# SoM-Connectors.net
KiCad netlist of a schematic drawn in Altium Designer
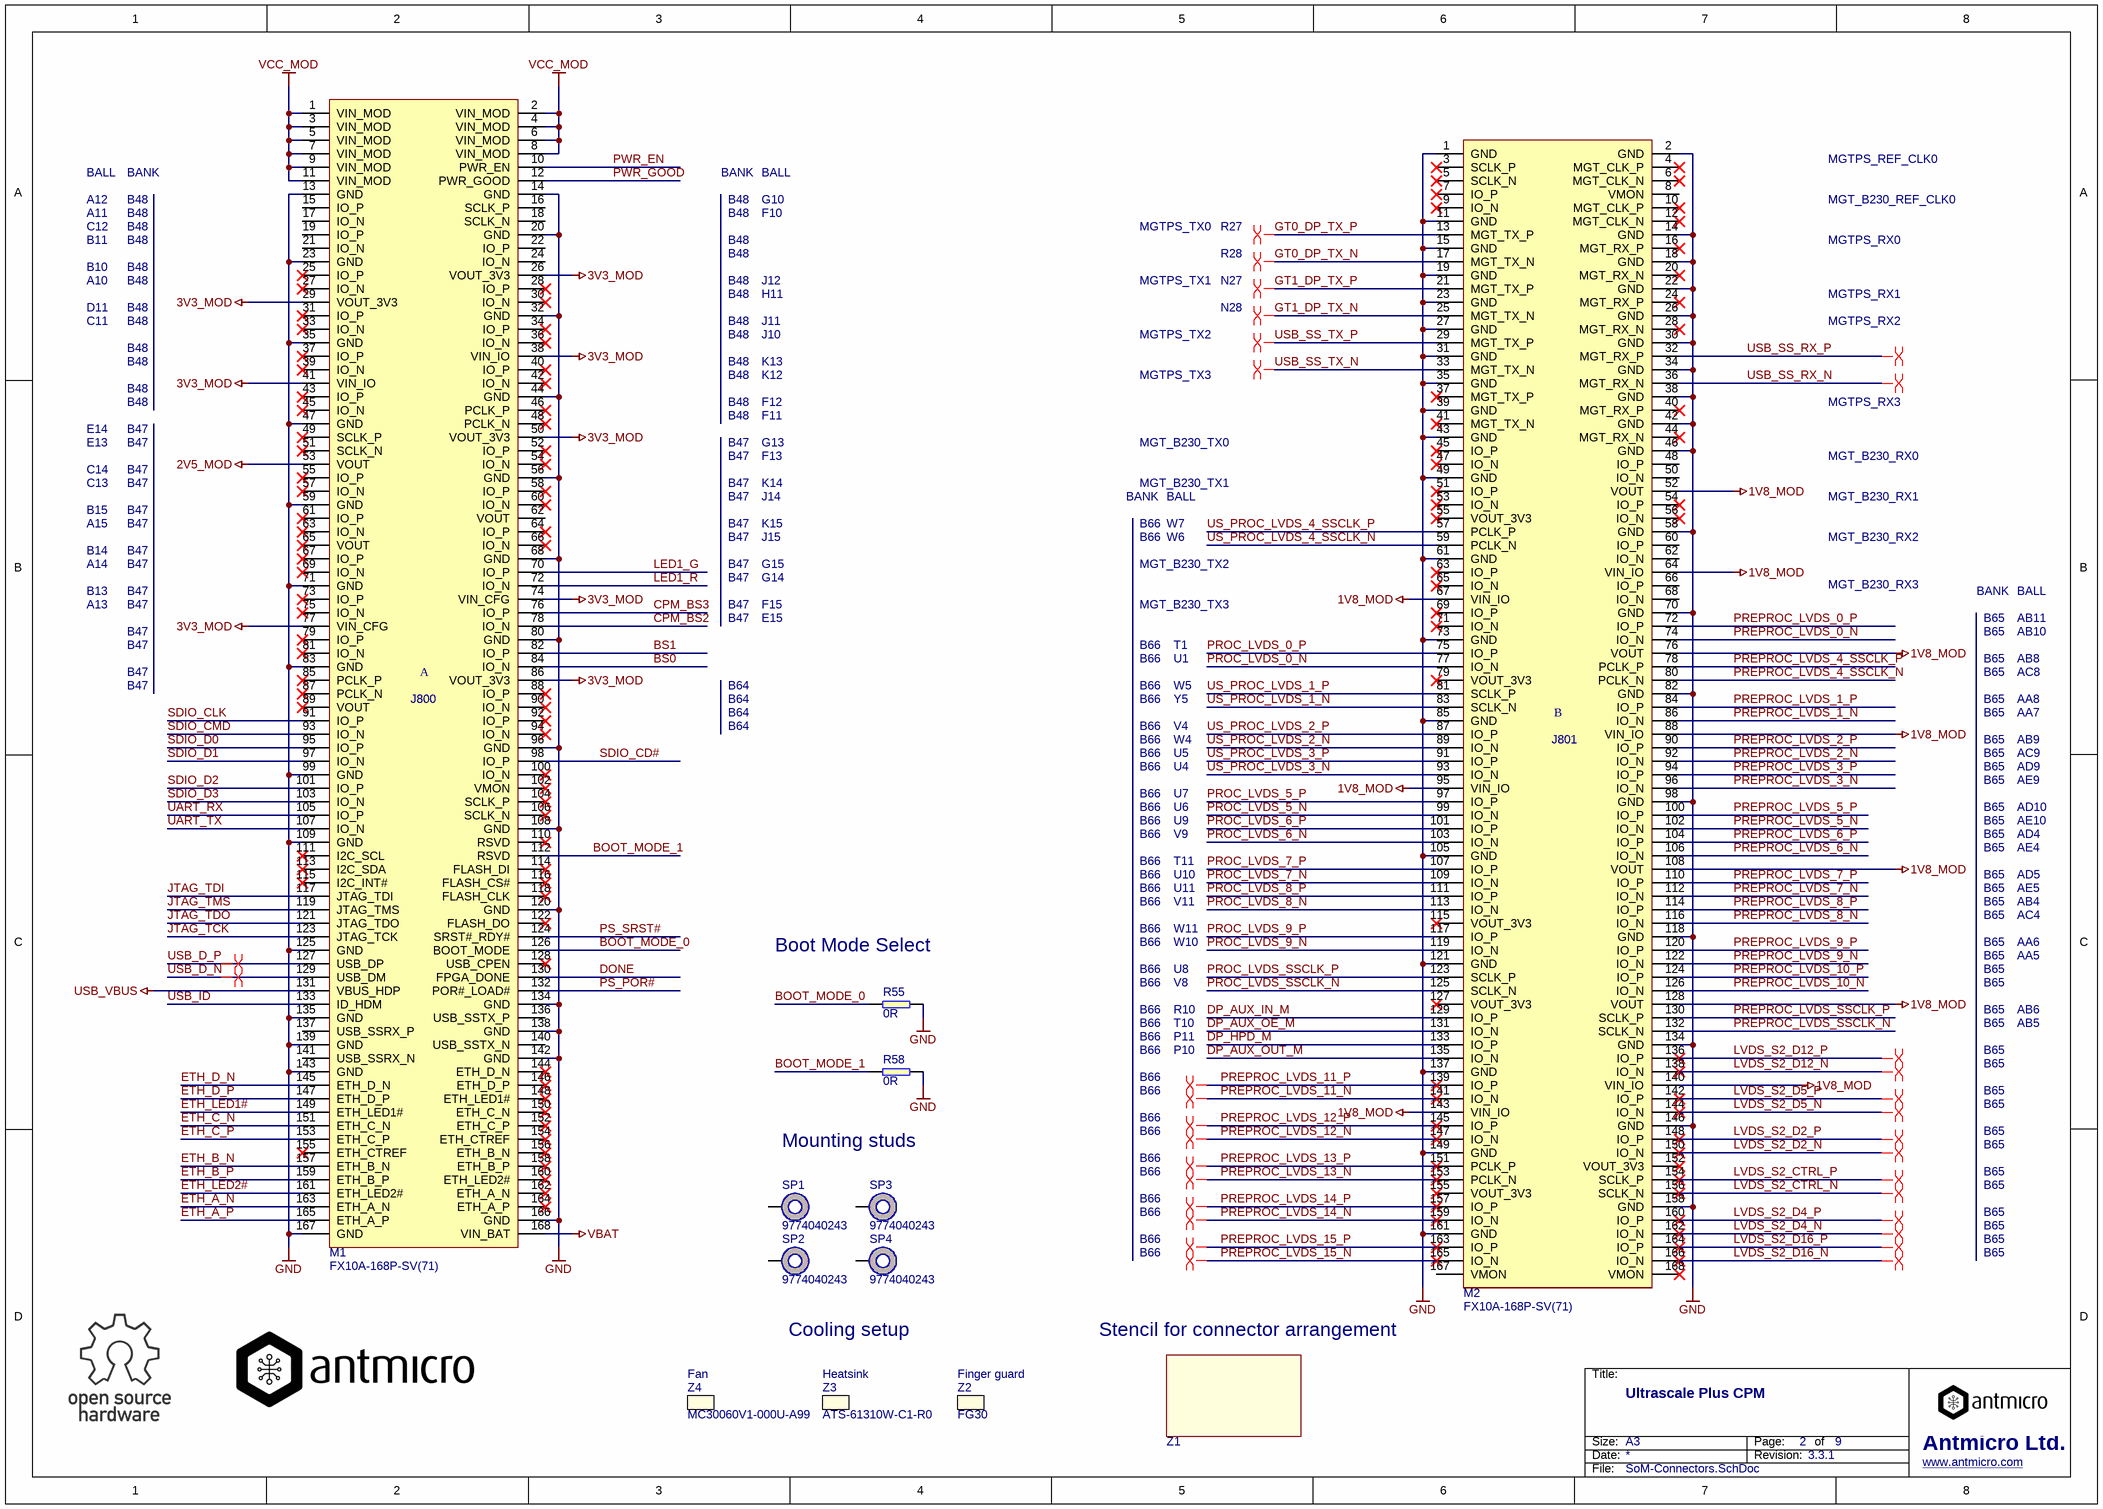
[diagram p0: SoM-Connectors.SchDoc]

(export (version "E")
  (design (tool "Eeschema 10.0.6"))
  (components
    (comp (ref "M1")
      (value "FX10A-168P-SV(71)")
      (footprint "HIROSE_FX10A-168P-SV(71)")
      (description "Enclustra Mercury Ultrascale connector")
      (fields (field (name "PART NUMBER") "Mercury_US1_A") (field (name "MANUFACTURER") "Hirose"))
      (libsource (lib "US-Plus-CPM") (part "Mercury_US1_A"))
    )
    (comp (ref "M2")
      (value "FX10A-168P-SV(71)")
      (footprint "HIROSE_FX10A-168P-SV(71)")
      (description "Enclustra Mercury Ultrascale connector")
      (fields (field (name "PART NUMBER") "Mercury_US1_B") (field (name "MANUFACTURER") "Hirose"))
      (libsource (lib "US-Plus-CPM") (part "Mercury_US1_B"))
    )
    (comp (ref "R55")
      (value "0R")
      (footprint "0603")
      (description "SMT Resistor 0R 0603")
      (fields (field (name "PART NUMBER") "R_0R_0603") (field (name "MANUFACTURER") "BOURNS"))
      (libsource (lib "US-Plus-CPM") (part "R"))
    )
    (comp (ref "R58")
      (value "0R")
      (footprint "0603")
      (description "SMT Resistor 0R 0603")
      (fields (field (name "PART NUMBER") "R_0R_0603") (field (name "MANUFACTURER") "BOURNS"))
      (libsource (lib "US-Plus-CPM") (part "R"))
    )
    (comp (ref "SP1")
      (value "9774040243")
      (footprint "M2-4mm")
      (description "M2x4")
      (fields (field (name "PART NUMBER") "WE_9774040243") (field (name "MANUFACTURER") "WURTH ELEKTRONIK"))
      (libsource (lib "US-Plus-CPM") (part "SPACER"))
    )
    (comp (ref "SP2")
      (value "9774040243")
      (footprint "M2-4mm")
      (description "M2x4")
      (fields (field (name "PART NUMBER") "WE_9774040243") (field (name "MANUFACTURER") "WURTH ELEKTRONIK"))
      (libsource (lib "US-Plus-CPM") (part "SPACER"))
    )
    (comp (ref "SP3")
      (value "9774040243")
      (footprint "M2-4mm")
      (description "M2x4")
      (fields (field (name "PART NUMBER") "WE_9774040243") (field (name "MANUFACTURER") "WURTH ELEKTRONIK"))
      (libsource (lib "US-Plus-CPM") (part "SPACER"))
    )
    (comp (ref "SP4")
      (value "9774040243")
      (footprint "M2-4mm")
      (description "M2x4")
      (fields (field (name "PART NUMBER") "WE_9774040243") (field (name "MANUFACTURER") "WURTH ELEKTRONIK"))
      (libsource (lib "US-Plus-CPM") (part "SPACER"))
    )
    (comp (ref "Z1")
      (value "Mechanical")
      (footprint "mercury_74x54_module")
      (fields (field (name "PART NUMBER") "MercuryModule_74x54"))
      (libsource (lib "US-Plus-CPM") (part "enclustra_mercury_74x54_module"))
    )
    (comp (ref "Z2")
      (value "FG30")
      (description "Fan Finger Guard, Grille, 30mm 30mm 24mm, steel")
      (fields (field (name "MANUFACTURER") "SEPA"))
      (libsource (lib "US-Plus-CPM") (part "GENERIC_BOM_ONLY"))
    )
    (comp (ref "Z3")
      (value "ATS-61310W-C1-R0")
      (description "Heat Sinks FANSINK ASSY 30.25 X 30.25 X 24.5 (MM)")
      (fields (field (name "MANUFACTURER") "Advanced Thermal Solution"))
      (libsource (lib "US-Plus-CPM") (part "GENERIC_BOM_ONLY"))
    )
    (comp (ref "Z4")
      (value "MC30060V1-000U-A99")
      (description "Fan: DC; axial; 5VDC; 30x30x6mm; 8.32m3/h; 28dBA; Vapo; 3.55mmH2O")
      (fields (field (name "MANUFACTURER") "SUNON"))
      (libsource (lib "US-Plus-CPM") (part "GENERIC_BOM_ONLY"))
    )
  )
  (nets
    (net (code "1") (name "/BOOT_MODE_0") (class "Default")
      (node (ref "M1") (pin "126") (pinfunction "BOOT_MODE_126") (pintype "passive"))
      (node (ref "R55") (pin "1") (pintype "passive"))
    )
    (net (code "2") (name "/BOOT_MODE_1") (class "Default")
      (node (ref "M1") (pin "112") (pinfunction "RSVD_112") (pintype "passive"))
      (node (ref "R58") (pin "1") (pintype "passive"))
    )
    (net (code "3") (name "/BS0") (class "Default")
      (node (ref "M1") (pin "84") (pinfunction "IO_N_84") (pintype "passive"))
    )
    (net (code "4") (name "/BS1") (class "Default")
      (node (ref "M1") (pin "82") (pinfunction "IO_P_82") (pintype "passive"))
    )
    (net (code "5") (name "/CPM_BS2") (class "Default")
      (node (ref "M1") (pin "78") (pinfunction "IO_N_78") (pintype "passive"))
    )
    (net (code "6") (name "/CPM_BS3") (class "Default")
      (node (ref "M1") (pin "76") (pinfunction "IO_P_76") (pintype "passive"))
    )
    (net (code "7") (name "/DONE") (class "Default")
      (node (ref "M1") (pin "130") (pinfunction "FPGA_DONE_130") (pintype "passive"))
    )
    (net (code "8") (name "/DP_AUX_IN_M") (class "Default")
      (node (ref "M2") (pin "129") (pinfunction "IO_P_129") (pintype "passive"))
    )
    (net (code "9") (name "/DP_AUX_OE_M") (class "Default")
      (node (ref "M2") (pin "131") (pinfunction "IO_N_131") (pintype "passive"))
    )
    (net (code "10") (name "/DP_AUX_OUT_M") (class "Default")
      (node (ref "M2") (pin "135") (pinfunction "IO_N_135") (pintype "passive"))
    )
    (net (code "11") (name "/DP_HPD_M") (class "Default")
      (node (ref "M2") (pin "133") (pinfunction "IO_P_133") (pintype "passive"))
    )
    (net (code "12") (name "/ETH_A_N") (class "Default")
      (node (ref "M1") (pin "163") (pinfunction "ETH_A_N_163") (pintype "passive"))
    )
    (net (code "13") (name "/ETH_A_P") (class "Default")
      (node (ref "M1") (pin "165") (pinfunction "ETH_A_P_165") (pintype "passive"))
    )
    (net (code "14") (name "/ETH_B_N") (class "Default")
      (node (ref "M1") (pin "157") (pinfunction "ETH_B_N_157") (pintype "passive"))
    )
    (net (code "15") (name "/ETH_B_P") (class "Default")
      (node (ref "M1") (pin "159") (pinfunction "ETH_B_P_159") (pintype "passive"))
    )
    (net (code "16") (name "/ETH_C_N") (class "Default")
      (node (ref "M1") (pin "151") (pinfunction "ETH_C_N_151") (pintype "passive"))
    )
    (net (code "17") (name "/ETH_C_P") (class "Default")
      (node (ref "M1") (pin "153") (pinfunction "ETH_C_P_153") (pintype "passive"))
    )
    (net (code "18") (name "/ETH_D_N") (class "Default")
      (node (ref "M1") (pin "145") (pinfunction "ETH_D_N_145") (pintype "passive"))
    )
    (net (code "19") (name "/ETH_D_P") (class "Default")
      (node (ref "M1") (pin "147") (pinfunction "ETH_D_P_147") (pintype "passive"))
    )
    (net (code "20") (name "/ETH_LED1#") (class "Default")
      (node (ref "M1") (pin "149") (pinfunction "ETH_LED1#_149") (pintype "passive"))
    )
    (net (code "21") (name "/ETH_LED2#") (class "Default")
      (node (ref "M1") (pin "161") (pinfunction "ETH_LED2#_161") (pintype "passive"))
    )
    (net (code "22") (name "/GT0_DP_TX_N") (class "Default")
      (node (ref "M2") (pin "17") (pinfunction "MGT_TX_N_17") (pintype "passive"))
    )
    (net (code "23") (name "/GT0_DP_TX_P") (class "Default")
      (node (ref "M2") (pin "13") (pinfunction "MGT_TX_P_13") (pintype "passive"))
    )
    (net (code "24") (name "/GT1_DP_TX_N") (class "Default")
      (node (ref "M2") (pin "25") (pinfunction "MGT_TX_N_25") (pintype "passive"))
    )
    (net (code "25") (name "/GT1_DP_TX_P") (class "Default")
      (node (ref "M2") (pin "21") (pinfunction "MGT_TX_P_21") (pintype "passive"))
    )
    (net (code "26") (name "/JTAG_TCK") (class "Default")
      (node (ref "M1") (pin "123") (pinfunction "JTAG_TCK_123") (pintype "passive"))
    )
    (net (code "27") (name "/JTAG_TDI") (class "Default")
      (node (ref "M1") (pin "117") (pinfunction "JTAG_TDI_117") (pintype "passive"))
    )
    (net (code "28") (name "/JTAG_TDO") (class "Default")
      (node (ref "M1") (pin "121") (pinfunction "JTAG_TDO_121") (pintype "passive"))
    )
    (net (code "29") (name "/JTAG_TMS") (class "Default")
      (node (ref "M1") (pin "119") (pinfunction "JTAG_TMS_119") (pintype "passive"))
    )
    (net (code "30") (name "/LED1_G") (class "Default")
      (node (ref "M1") (pin "70") (pinfunction "IO_P_70") (pintype "passive"))
    )
    (net (code "31") (name "/LED1_R") (class "Default")
      (node (ref "M1") (pin "72") (pinfunction "IO_N_72") (pintype "passive"))
    )
    (net (code "32") (name "/LVDS_S2_CTRL_N") (class "Default")
      (node (ref "M2") (pin "156") (pinfunction "SCLK_N_156") (pintype "passive+no_connect"))
    )
    (net (code "33") (name "/LVDS_S2_CTRL_P") (class "Default")
      (node (ref "M2") (pin "154") (pinfunction "SCLK_P_154") (pintype "passive+no_connect"))
    )
    (net (code "34") (name "/LVDS_S2_D2_N") (class "Default")
      (node (ref "M2") (pin "150") (pinfunction "IO_N_150") (pintype "passive+no_connect"))
    )
    (net (code "35") (name "/LVDS_S2_D2_P") (class "Default")
      (node (ref "M2") (pin "148") (pinfunction "IO_P_148") (pintype "passive+no_connect"))
    )
    (net (code "36") (name "/LVDS_S2_D4_N") (class "Default")
      (node (ref "M2") (pin "162") (pinfunction "IO_N_162") (pintype "passive+no_connect"))
    )
    (net (code "37") (name "/LVDS_S2_D4_P") (class "Default")
      (node (ref "M2") (pin "160") (pinfunction "IO_P_160") (pintype "passive+no_connect"))
    )
    (net (code "38") (name "/LVDS_S2_D5_N") (class "Default")
      (node (ref "M2") (pin "144") (pinfunction "IO_N_144") (pintype "passive+no_connect"))
    )
    (net (code "39") (name "/LVDS_S2_D5_P") (class "Default")
      (node (ref "M2") (pin "142") (pinfunction "IO_P_142") (pintype "passive+no_connect"))
    )
    (net (code "40") (name "/LVDS_S2_D12_N") (class "Default")
      (node (ref "M2") (pin "138") (pinfunction "IO_N_138") (pintype "passive+no_connect"))
    )
    (net (code "41") (name "/LVDS_S2_D12_P") (class "Default")
      (node (ref "M2") (pin "136") (pinfunction "IO_P_136") (pintype "passive+no_connect"))
    )
    (net (code "42") (name "/LVDS_S2_D16_N") (class "Default")
      (node (ref "M2") (pin "166") (pinfunction "IO_N_166") (pintype "passive+no_connect"))
    )
    (net (code "43") (name "/LVDS_S2_D16_P") (class "Default")
      (node (ref "M2") (pin "164") (pinfunction "IO_P_164") (pintype "passive+no_connect"))
    )
    (net (code "44") (name "/PREPROC_LVDS_0_N") (class "Default")
      (node (ref "M2") (pin "74") (pinfunction "IO_N_74") (pintype "passive"))
    )
    (net (code "45") (name "/PREPROC_LVDS_0_P") (class "Default")
      (node (ref "M2") (pin "72") (pinfunction "IO_P_72") (pintype "passive"))
    )
    (net (code "46") (name "/PREPROC_LVDS_1_N") (class "Default")
      (node (ref "M2") (pin "86") (pinfunction "IO_N_86") (pintype "passive"))
    )
    (net (code "47") (name "/PREPROC_LVDS_1_P") (class "Default")
      (node (ref "M2") (pin "84") (pinfunction "IO_P_84") (pintype "passive"))
    )
    (net (code "48") (name "/PREPROC_LVDS_2_N") (class "Default")
      (node (ref "M2") (pin "92") (pinfunction "IO_N_92") (pintype "passive"))
    )
    (net (code "49") (name "/PREPROC_LVDS_2_P") (class "Default")
      (node (ref "M2") (pin "90") (pinfunction "IO_P_90") (pintype "passive"))
    )
    (net (code "50") (name "/PREPROC_LVDS_3_N") (class "Default")
      (node (ref "M2") (pin "96") (pinfunction "IO_N_96") (pintype "passive"))
    )
    (net (code "51") (name "/PREPROC_LVDS_3_P") (class "Default")
      (node (ref "M2") (pin "94") (pinfunction "IO_P_94") (pintype "passive"))
    )
    (net (code "52") (name "/PREPROC_LVDS_4_SSCLK_N") (class "Default")
      (node (ref "M2") (pin "80") (pinfunction "PCLK_N_80") (pintype "passive"))
    )
    (net (code "53") (name "/PREPROC_LVDS_4_SSCLK_P") (class "Default")
      (node (ref "M2") (pin "78") (pinfunction "PCLK_P_78") (pintype "passive"))
    )
    (net (code "54") (name "/PREPROC_LVDS_5_N") (class "Default")
      (node (ref "M2") (pin "102") (pinfunction "IO_N_102") (pintype "passive"))
    )
    (net (code "55") (name "/PREPROC_LVDS_5_P") (class "Default")
      (node (ref "M2") (pin "100") (pinfunction "IO_P_100") (pintype "passive"))
    )
    (net (code "56") (name "/PREPROC_LVDS_6_N") (class "Default")
      (node (ref "M2") (pin "106") (pinfunction "IO_N_106") (pintype "passive"))
    )
    (net (code "57") (name "/PREPROC_LVDS_6_P") (class "Default")
      (node (ref "M2") (pin "104") (pinfunction "IO_P_104") (pintype "passive"))
    )
    (net (code "58") (name "/PREPROC_LVDS_7_N") (class "Default")
      (node (ref "M2") (pin "112") (pinfunction "IO_N_112") (pintype "passive"))
    )
    (net (code "59") (name "/PREPROC_LVDS_7_P") (class "Default")
      (node (ref "M2") (pin "110") (pinfunction "IO_P_110") (pintype "passive"))
    )
    (net (code "60") (name "/PREPROC_LVDS_8_N") (class "Default")
      (node (ref "M2") (pin "116") (pinfunction "IO_N_116") (pintype "passive"))
    )
    (net (code "61") (name "/PREPROC_LVDS_8_P") (class "Default")
      (node (ref "M2") (pin "114") (pinfunction "IO_P_114") (pintype "passive"))
    )
    (net (code "62") (name "/PREPROC_LVDS_9_N") (class "Default")
      (node (ref "M2") (pin "122") (pinfunction "IO_N_122") (pintype "passive"))
    )
    (net (code "63") (name "/PREPROC_LVDS_9_P") (class "Default")
      (node (ref "M2") (pin "120") (pinfunction "IO_P_120") (pintype "passive"))
    )
    (net (code "64") (name "/PREPROC_LVDS_10_N") (class "Default")
      (node (ref "M2") (pin "126") (pinfunction "IO_N_126") (pintype "passive"))
    )
    (net (code "65") (name "/PREPROC_LVDS_10_P") (class "Default")
      (node (ref "M2") (pin "124") (pinfunction "IO_P_124") (pintype "passive"))
    )
    (net (code "66") (name "/PREPROC_LVDS_11_N") (class "Default")
      (node (ref "M2") (pin "141") (pinfunction "IO_N_141") (pintype "passive+no_connect"))
    )
    (net (code "67") (name "/PREPROC_LVDS_11_P") (class "Default")
      (node (ref "M2") (pin "139") (pinfunction "IO_P_139") (pintype "passive+no_connect"))
    )
    (net (code "68") (name "/PREPROC_LVDS_12_N") (class "Default")
      (node (ref "M2") (pin "147") (pinfunction "IO_N_147") (pintype "passive+no_connect"))
    )
    (net (code "69") (name "/PREPROC_LVDS_12_P") (class "Default")
      (node (ref "M2") (pin "145") (pinfunction "IO_P_145") (pintype "passive+no_connect"))
    )
    (net (code "70") (name "/PREPROC_LVDS_13_N") (class "Default")
      (node (ref "M2") (pin "153") (pinfunction "PCLK_N_153") (pintype "passive+no_connect"))
    )
    (net (code "71") (name "/PREPROC_LVDS_13_P") (class "Default")
      (node (ref "M2") (pin "151") (pinfunction "PCLK_P_151") (pintype "passive+no_connect"))
    )
    (net (code "72") (name "/PREPROC_LVDS_14_N") (class "Default")
      (node (ref "M2") (pin "159") (pinfunction "IO_N_159") (pintype "passive+no_connect"))
    )
    (net (code "73") (name "/PREPROC_LVDS_14_P") (class "Default")
      (node (ref "M2") (pin "157") (pinfunction "IO_P_157") (pintype "passive+no_connect"))
    )
    (net (code "74") (name "/PREPROC_LVDS_15_N") (class "Default")
      (node (ref "M2") (pin "165") (pinfunction "IO_N_165") (pintype "passive+no_connect"))
    )
    (net (code "75") (name "/PREPROC_LVDS_15_P") (class "Default")
      (node (ref "M2") (pin "163") (pinfunction "IO_P_163") (pintype "passive+no_connect"))
    )
    (net (code "76") (name "/PREPROC_LVDS_SSCLK_N") (class "Default")
      (node (ref "M2") (pin "132") (pinfunction "SCLK_N_132") (pintype "passive"))
    )
    (net (code "77") (name "/PREPROC_LVDS_SSCLK_P") (class "Default")
      (node (ref "M2") (pin "130") (pinfunction "SCLK_P_130") (pintype "passive"))
    )
    (net (code "78") (name "/PROC_LVDS_0_N") (class "Default")
      (node (ref "M2") (pin "77") (pinfunction "IO_N_77") (pintype "passive"))
    )
    (net (code "79") (name "/PROC_LVDS_0_P") (class "Default")
      (node (ref "M2") (pin "75") (pinfunction "IO_P_75") (pintype "passive"))
    )
    (net (code "80") (name "/PROC_LVDS_5_N") (class "Default")
      (node (ref "M2") (pin "99") (pinfunction "IO_N_99") (pintype "passive"))
    )
    (net (code "81") (name "/PROC_LVDS_5_P") (class "Default")
      (node (ref "M2") (pin "97") (pinfunction "IO_P_97") (pintype "passive"))
    )
    (net (code "82") (name "/PROC_LVDS_6_N") (class "Default")
      (node (ref "M2") (pin "103") (pinfunction "IO_N_103") (pintype "passive"))
    )
    (net (code "83") (name "/PROC_LVDS_6_P") (class "Default")
      (node (ref "M2") (pin "101") (pinfunction "IO_P_101") (pintype "passive"))
    )
    (net (code "84") (name "/PROC_LVDS_7_N") (class "Default")
      (node (ref "M2") (pin "109") (pinfunction "IO_N_109") (pintype "passive"))
    )
    (net (code "85") (name "/PROC_LVDS_7_P") (class "Default")
      (node (ref "M2") (pin "107") (pinfunction "IO_P_107") (pintype "passive"))
    )
    (net (code "86") (name "/PROC_LVDS_8_N") (class "Default")
      (node (ref "M2") (pin "113") (pinfunction "IO_N_113") (pintype "passive"))
    )
    (net (code "87") (name "/PROC_LVDS_8_P") (class "Default")
      (node (ref "M2") (pin "111") (pinfunction "IO_P_111") (pintype "passive"))
    )
    (net (code "88") (name "/PROC_LVDS_9_N") (class "Default")
      (node (ref "M2") (pin "119") (pinfunction "IO_N_119") (pintype "passive"))
    )
    (net (code "89") (name "/PROC_LVDS_9_P") (class "Default")
      (node (ref "M2") (pin "117") (pinfunction "IO_P_117") (pintype "passive"))
    )
    (net (code "90") (name "/PROC_LVDS_SSCLK_N") (class "Default")
      (node (ref "M2") (pin "125") (pinfunction "SCLK_N_125") (pintype "passive"))
    )
    (net (code "91") (name "/PROC_LVDS_SSCLK_P") (class "Default")
      (node (ref "M2") (pin "123") (pinfunction "SCLK_P_123") (pintype "passive"))
    )
    (net (code "92") (name "/PS_POR#") (class "Default")
      (node (ref "M1") (pin "132") (pinfunction "POR#_LOAD#_132") (pintype "passive"))
    )
    (net (code "93") (name "/PS_SRST#") (class "Default")
      (node (ref "M1") (pin "124") (pinfunction "SRST#_RDY#_124") (pintype "passive"))
    )
    (net (code "94") (name "/PWR_EN") (class "Default")
      (node (ref "M1") (pin "10") (pinfunction "PWR_EN_10") (pintype "passive"))
    )
    (net (code "95") (name "/PWR_GOOD") (class "Default")
      (node (ref "M1") (pin "12") (pinfunction "PWR_GOOD_12") (pintype "passive"))
    )
    (net (code "96") (name "/SDIO_CD#") (class "Default")
      (node (ref "M1") (pin "98") (pinfunction "IO_P_98") (pintype "passive"))
    )
    (net (code "97") (name "/SDIO_CLK") (class "Default")
      (node (ref "M1") (pin "91") (pinfunction "IO_P_91") (pintype "passive"))
    )
    (net (code "98") (name "/SDIO_CMD") (class "Default")
      (node (ref "M1") (pin "93") (pinfunction "IO_N_93") (pintype "passive"))
    )
    (net (code "99") (name "/SDIO_D0") (class "Default")
      (node (ref "M1") (pin "95") (pinfunction "IO_P_95") (pintype "passive"))
    )
    (net (code "100") (name "/SDIO_D1") (class "Default")
      (node (ref "M1") (pin "97") (pinfunction "IO_N_97") (pintype "passive"))
    )
    (net (code "101") (name "/SDIO_D2") (class "Default")
      (node (ref "M1") (pin "101") (pinfunction "IO_P_101") (pintype "passive"))
    )
    (net (code "102") (name "/SDIO_D3") (class "Default")
      (node (ref "M1") (pin "103") (pinfunction "IO_N_103") (pintype "passive"))
    )
    (net (code "103") (name "/UART_RX") (class "Default")
      (node (ref "M1") (pin "105") (pinfunction "IO_P_105") (pintype "passive"))
    )
    (net (code "104") (name "/UART_TX") (class "Default")
      (node (ref "M1") (pin "107") (pinfunction "IO_N_107") (pintype "passive"))
    )
    (net (code "105") (name "/USB_D_N") (class "Default")
      (node (ref "M1") (pin "129") (pinfunction "USB_DM_129") (pintype "passive"))
    )
    (net (code "106") (name "/USB_D_P") (class "Default")
      (node (ref "M1") (pin "127") (pinfunction "USB_DP_127") (pintype "passive"))
    )
    (net (code "107") (name "/USB_ID") (class "Default")
      (node (ref "M1") (pin "133") (pinfunction "ID_HDM_133") (pintype "passive"))
    )
    (net (code "108") (name "/USB_SS_RX_N") (class "Default")
      (node (ref "M2") (pin "36") (pinfunction "MGT_RX_N_36") (pintype "passive"))
    )
    (net (code "109") (name "/USB_SS_RX_P") (class "Default")
      (node (ref "M2") (pin "32") (pinfunction "MGT_RX_P_32") (pintype "passive"))
    )
    (net (code "110") (name "/USB_SS_TX_N") (class "Default")
      (node (ref "M2") (pin "33") (pinfunction "MGT_TX_N_33") (pintype "passive"))
    )
    (net (code "111") (name "/USB_SS_TX_P") (class "Default")
      (node (ref "M2") (pin "29") (pinfunction "MGT_TX_P_29") (pintype "passive"))
    )
    (net (code "112") (name "/US_PROC_LVDS_1_N") (class "Default")
      (node (ref "M2") (pin "83") (pinfunction "SCLK_N_83") (pintype "passive"))
    )
    (net (code "113") (name "/US_PROC_LVDS_1_P") (class "Default")
      (node (ref "M2") (pin "81") (pinfunction "SCLK_P_81") (pintype "passive"))
    )
    (net (code "114") (name "/US_PROC_LVDS_2_N") (class "Default")
      (node (ref "M2") (pin "89") (pinfunction "IO_N_89") (pintype "passive"))
    )
    (net (code "115") (name "/US_PROC_LVDS_2_P") (class "Default")
      (node (ref "M2") (pin "87") (pinfunction "IO_P_87") (pintype "passive"))
    )
    (net (code "116") (name "/US_PROC_LVDS_3_N") (class "Default")
      (node (ref "M2") (pin "93") (pinfunction "IO_N_93") (pintype "passive"))
    )
    (net (code "117") (name "/US_PROC_LVDS_3_P") (class "Default")
      (node (ref "M2") (pin "91") (pinfunction "IO_P_91") (pintype "passive"))
    )
    (net (code "118") (name "/US_PROC_LVDS_4_SSCLK_N") (class "Default")
      (node (ref "M2") (pin "59") (pinfunction "PCLK_N_59") (pintype "passive"))
    )
    (net (code "119") (name "/US_PROC_LVDS_4_SSCLK_P") (class "Default")
      (node (ref "M2") (pin "57") (pinfunction "PCLK_P_57") (pintype "passive"))
    )
    (net (code "120") (name "1V8_MOD") (class "Default")
      (node (ref "M2") (pin "108") (pinfunction "VOUT_108") (pintype "passive"))
      (node (ref "M2") (pin "128") (pinfunction "VOUT_128") (pintype "passive"))
      (node (ref "M2") (pin "140") (pinfunction "VIN_IO_140") (pintype "passive"))
      (node (ref "M2") (pin "143") (pinfunction "VIN_IO_143") (pintype "passive"))
      (node (ref "M2") (pin "52") (pinfunction "VOUT_52") (pintype "passive"))
      (node (ref "M2") (pin "64") (pinfunction "VIN_IO_64") (pintype "passive"))
      (node (ref "M2") (pin "67") (pinfunction "VIN_IO_67") (pintype "passive"))
      (node (ref "M2") (pin "76") (pinfunction "VOUT_76") (pintype "passive"))
      (node (ref "M2") (pin "88") (pinfunction "VIN_IO_88") (pintype "passive"))
      (node (ref "M2") (pin "95") (pinfunction "VIN_IO_95") (pintype "passive"))
    )
    (net (code "121") (name "2V5_MOD") (class "Default")
      (node (ref "M1") (pin "53") (pinfunction "VOUT_53") (pintype "power_in"))
    )
    (net (code "122") (name "3V3_MOD") (class "Default")
      (node (ref "M1") (pin "26") (pinfunction "VOUT_3V3_26") (pintype "power_in"))
      (node (ref "M1") (pin "29") (pinfunction "VOUT_3V3_29") (pintype "power_in"))
      (node (ref "M1") (pin "38") (pinfunction "VIN_IO_38") (pintype "power_in"))
      (node (ref "M1") (pin "41") (pinfunction "VIN_IO_41") (pintype "power_in"))
      (node (ref "M1") (pin "50") (pinfunction "VOUT_3V3_50") (pintype "power_in"))
      (node (ref "M1") (pin "74") (pinfunction "VIN_CFG_74") (pintype "power_in"))
      (node (ref "M1") (pin "77") (pinfunction "VIN_CFG_77") (pintype "power_in"))
      (node (ref "M1") (pin "86") (pinfunction "VOUT_3V3_86") (pintype "power_in"))
    )
    (net (code "123") (name "GND") (class "Default")
      (node (ref "M1") (pin "108") (pinfunction "GND_108") (pintype "power_in"))
      (node (ref "M1") (pin "109") (pinfunction "GND_109") (pintype "power_in"))
      (node (ref "M1") (pin "120") (pinfunction "GND_120") (pintype "power_in"))
      (node (ref "M1") (pin "125") (pinfunction "GND_125") (pintype "power_in"))
      (node (ref "M1") (pin "13") (pinfunction "GND_13") (pintype "power_in"))
      (node (ref "M1") (pin "134") (pinfunction "GND_134") (pintype "power_in"))
      (node (ref "M1") (pin "135") (pinfunction "GND_135") (pintype "power_in"))
      (node (ref "M1") (pin "138") (pinfunction "GND_138") (pintype "power_in"))
      (node (ref "M1") (pin "139") (pinfunction "GND_139") (pintype "power_in"))
      (node (ref "M1") (pin "14") (pinfunction "GND_14") (pintype "power_in"))
      (node (ref "M1") (pin "142") (pinfunction "GND_142") (pintype "power_in"))
      (node (ref "M1") (pin "143") (pinfunction "GND_143") (pintype "power_in"))
      (node (ref "M1") (pin "166") (pinfunction "GND_166") (pintype "power_in"))
      (node (ref "M1") (pin "167") (pinfunction "GND_167") (pintype "power_in"))
      (node (ref "M1") (pin "20") (pinfunction "GND_20") (pintype "power_in"))
      (node (ref "M1") (pin "23") (pinfunction "GND_23") (pintype "power_in"))
      (node (ref "M1") (pin "32") (pinfunction "GND_32") (pintype "power_in"))
      (node (ref "M1") (pin "35") (pinfunction "GND_35") (pintype "power_in"))
      (node (ref "M1") (pin "44") (pinfunction "GND_44") (pintype "power_in"))
      (node (ref "M1") (pin "47") (pinfunction "GND_47") (pintype "power_in"))
      (node (ref "M1") (pin "56") (pinfunction "GND_56") (pintype "power_in"))
      (node (ref "M1") (pin "59") (pinfunction "GND_59") (pintype "power_in"))
      (node (ref "M1") (pin "68") (pinfunction "GND_68") (pintype "power_in"))
      (node (ref "M1") (pin "71") (pinfunction "GND_71") (pintype "power_in"))
      (node (ref "M1") (pin "80") (pinfunction "GND_80") (pintype "power_in"))
      (node (ref "M1") (pin "83") (pinfunction "GND_83") (pintype "power_in"))
      (node (ref "M1") (pin "96") (pinfunction "GND_96") (pintype "power_in"))
      (node (ref "M1") (pin "99") (pinfunction "GND_99") (pintype "power_in"))
      (node (ref "M2") (pin "1") (pinfunction "GND_1") (pintype "passive"))
      (node (ref "M2") (pin "105") (pinfunction "GND_105") (pintype "passive"))
      (node (ref "M2") (pin "11") (pinfunction "GND_11") (pintype "passive"))
      (node (ref "M2") (pin "118") (pinfunction "GND_118") (pintype "passive"))
      (node (ref "M2") (pin "121") (pinfunction "GND_121") (pintype "passive"))
      (node (ref "M2") (pin "134") (pinfunction "GND_134") (pintype "passive"))
      (node (ref "M2") (pin "137") (pinfunction "GND_137") (pintype "passive"))
      (node (ref "M2") (pin "14") (pinfunction "GND_14") (pintype "passive"))
      (node (ref "M2") (pin "146") (pinfunction "GND_146") (pintype "passive"))
      (node (ref "M2") (pin "149") (pinfunction "GND_149") (pintype "passive"))
      (node (ref "M2") (pin "15") (pinfunction "GND_15") (pintype "passive"))
      (node (ref "M2") (pin "158") (pinfunction "GND_158") (pintype "passive"))
      (node (ref "M2") (pin "161") (pinfunction "GND_161") (pintype "passive"))
      (node (ref "M2") (pin "18") (pinfunction "GND_18") (pintype "passive"))
      (node (ref "M2") (pin "19") (pinfunction "GND_19") (pintype "passive"))
      (node (ref "M2") (pin "2") (pinfunction "GND_2") (pintype "passive"))
      (node (ref "M2") (pin "22") (pinfunction "GND_22") (pintype "passive"))
      (node (ref "M2") (pin "23") (pinfunction "GND_23") (pintype "passive"))
      (node (ref "M2") (pin "26") (pinfunction "GND_26") (pintype "passive"))
      (node (ref "M2") (pin "27") (pinfunction "GND_27") (pintype "passive"))
      (node (ref "M2") (pin "30") (pinfunction "GND_30") (pintype "passive"))
      (node (ref "M2") (pin "31") (pinfunction "GND_31") (pintype "passive"))
      (node (ref "M2") (pin "34") (pinfunction "GND_34") (pintype "passive"))
      (node (ref "M2") (pin "35") (pinfunction "GND_35") (pintype "passive"))
      (node (ref "M2") (pin "38") (pinfunction "GND_38") (pintype "passive"))
      (node (ref "M2") (pin "39") (pinfunction "GND_39") (pintype "passive"))
      (node (ref "M2") (pin "42") (pinfunction "GND_42") (pintype "passive"))
      (node (ref "M2") (pin "43") (pinfunction "GND_43") (pintype "passive"))
      (node (ref "M2") (pin "46") (pinfunction "GND_46") (pintype "passive"))
      (node (ref "M2") (pin "49") (pinfunction "GND_49") (pintype "passive"))
      (node (ref "M2") (pin "58") (pinfunction "GND_58") (pintype "passive"))
      (node (ref "M2") (pin "61") (pinfunction "GND_61") (pintype "passive"))
      (node (ref "M2") (pin "70") (pinfunction "GND_70") (pintype "passive"))
      (node (ref "M2") (pin "73") (pinfunction "GND_73") (pintype "passive"))
      (node (ref "M2") (pin "82") (pinfunction "GND_82") (pintype "passive"))
      (node (ref "M2") (pin "85") (pinfunction "GND_85") (pintype "passive"))
      (node (ref "M2") (pin "98") (pinfunction "GND_98") (pintype "passive"))
      (node (ref "R55") (pin "2") (pintype "passive"))
      (node (ref "R58") (pin "2") (pintype "passive"))
    )
    (net (code "124") (name "USB_VBUS") (class "Default")
      (node (ref "M1") (pin "131") (pinfunction "VBUS_HDP_131") (pintype "passive"))
    )
    (net (code "125") (name "VBAT") (class "Default")
      (node (ref "M1") (pin "168") (pinfunction "VIN_BAT_168") (pintype "power_in"))
    )
    (net (code "126") (name "VCC_MOD") (class "Default")
      (node (ref "M1") (pin "1") (pinfunction "VIN_MOD_1") (pintype "power_in"))
      (node (ref "M1") (pin "11") (pinfunction "VIN_MOD_11") (pintype "power_in"))
      (node (ref "M1") (pin "2") (pinfunction "VIN_MOD_2") (pintype "power_in"))
      (node (ref "M1") (pin "3") (pinfunction "VIN_MOD_3") (pintype "power_in"))
      (node (ref "M1") (pin "4") (pinfunction "VIN_MOD_4") (pintype "power_in"))
      (node (ref "M1") (pin "5") (pinfunction "VIN_MOD_5") (pintype "power_in"))
      (node (ref "M1") (pin "6") (pinfunction "VIN_MOD_6") (pintype "power_in"))
      (node (ref "M1") (pin "7") (pinfunction "VIN_MOD_7") (pintype "power_in"))
      (node (ref "M1") (pin "8") (pinfunction "VIN_MOD_8") (pintype "power_in"))
      (node (ref "M1") (pin "9") (pinfunction "VIN_MOD_9") (pintype "power_in"))
    )
    (net (code "127") (name "unconnected-(M1-ETH_A_N-Pad162)") (class "Default")
      (node (ref "M1") (pin "162") (pinfunction "ETH_A_N_162") (pintype "passive+no_connect"))
    )
    (net (code "128") (name "unconnected-(M1-ETH_A_P-Pad164)") (class "Default")
      (node (ref "M1") (pin "164") (pinfunction "ETH_A_P_164") (pintype "passive+no_connect"))
    )
    (net (code "129") (name "unconnected-(M1-ETH_B_N-Pad156)") (class "Default")
      (node (ref "M1") (pin "156") (pinfunction "ETH_B_N_156") (pintype "passive+no_connect"))
    )
    (net (code "130") (name "unconnected-(M1-ETH_B_P-Pad158)") (class "Default")
      (node (ref "M1") (pin "158") (pinfunction "ETH_B_P_158") (pintype "passive+no_connect"))
    )
    (net (code "131") (name "unconnected-(M1-ETH_CTREF-Pad154)") (class "Default")
      (node (ref "M1") (pin "154") (pinfunction "ETH_CTREF_154") (pintype "passive+no_connect"))
    )
    (net (code "132") (name "unconnected-(M1-ETH_CTREF-Pad155)") (class "Default")
      (node (ref "M1") (pin "155") (pinfunction "ETH_CTREF_155") (pintype "passive+no_connect"))
    )
    (net (code "133") (name "unconnected-(M1-ETH_C_N-Pad150)") (class "Default")
      (node (ref "M1") (pin "150") (pinfunction "ETH_C_N_150") (pintype "passive+no_connect"))
    )
    (net (code "134") (name "unconnected-(M1-ETH_C_P-Pad152)") (class "Default")
      (node (ref "M1") (pin "152") (pinfunction "ETH_C_P_152") (pintype "passive+no_connect"))
    )
    (net (code "135") (name "unconnected-(M1-ETH_D_N-Pad144)") (class "Default")
      (node (ref "M1") (pin "144") (pinfunction "ETH_D_N_144") (pintype "passive+no_connect"))
    )
    (net (code "136") (name "unconnected-(M1-ETH_D_P-Pad146)") (class "Default")
      (node (ref "M1") (pin "146") (pinfunction "ETH_D_P_146") (pintype "passive+no_connect"))
    )
    (net (code "137") (name "unconnected-(M1-ETH_LED1#-Pad148)") (class "Default")
      (node (ref "M1") (pin "148") (pinfunction "ETH_LED1#_148") (pintype "passive+no_connect"))
    )
    (net (code "138") (name "unconnected-(M1-ETH_LED2#-Pad160)") (class "Default")
      (node (ref "M1") (pin "160") (pinfunction "ETH_LED2#_160") (pintype "passive+no_connect"))
    )
    (net (code "139") (name "unconnected-(M1-FLASH_CLK-Pad118)") (class "Default")
      (node (ref "M1") (pin "118") (pinfunction "FLASH_CLK_118") (pintype "passive+no_connect"))
    )
    (net (code "140") (name "unconnected-(M1-FLASH_CS#-Pad116)") (class "Default")
      (node (ref "M1") (pin "116") (pinfunction "FLASH_CS#_116") (pintype "passive+no_connect"))
    )
    (net (code "141") (name "unconnected-(M1-FLASH_DI-Pad114)") (class "Default")
      (node (ref "M1") (pin "114") (pinfunction "FLASH_DI_114") (pintype "passive+no_connect"))
    )
    (net (code "142") (name "unconnected-(M1-FLASH_DO-Pad122)") (class "Default")
      (node (ref "M1") (pin "122") (pinfunction "FLASH_DO_122") (pintype "passive+no_connect"))
    )
    (net (code "143") (name "unconnected-(M1-I2C_INT#-Pad115)") (class "Default")
      (node (ref "M1") (pin "115") (pinfunction "I2C_INT#_115") (pintype "passive+no_connect"))
    )
    (net (code "144") (name "unconnected-(M1-I2C_SCL-Pad111)") (class "Default")
      (node (ref "M1") (pin "111") (pinfunction "I2C_SCL_111") (pintype "passive+no_connect"))
    )
    (net (code "145") (name "unconnected-(M1-I2C_SDA-Pad113)") (class "Default")
      (node (ref "M1") (pin "113") (pinfunction "I2C_SDA_113") (pintype "passive+no_connect"))
    )
    (net (code "146") (name "unconnected-(M1-IO_N-Pad17)") (class "Default")
      (node (ref "M1") (pin "17") (pinfunction "IO_N_17") (pintype "passive"))
    )
    (net (code "147") (name "unconnected-(M1-IO_N-Pad21)") (class "Default")
      (node (ref "M1") (pin "21") (pinfunction "IO_N_21") (pintype "passive"))
    )
    (net (code "148") (name "unconnected-(M1-IO_N-Pad24)") (class "Default")
      (node (ref "M1") (pin "24") (pinfunction "IO_N_24") (pintype "passive"))
    )
    (net (code "149") (name "unconnected-(M1-IO_N-Pad27)") (class "Default")
      (node (ref "M1") (pin "27") (pinfunction "IO_N_27") (pintype "passive+no_connect"))
    )
    (net (code "150") (name "unconnected-(M1-IO_N-Pad30)") (class "Default")
      (node (ref "M1") (pin "30") (pinfunction "IO_N_30") (pintype "passive+no_connect"))
    )
    (net (code "151") (name "unconnected-(M1-IO_N-Pad33)") (class "Default")
      (node (ref "M1") (pin "33") (pinfunction "IO_N_33") (pintype "passive+no_connect"))
    )
    (net (code "152") (name "unconnected-(M1-IO_N-Pad36)") (class "Default")
      (node (ref "M1") (pin "36") (pinfunction "IO_N_36") (pintype "passive+no_connect"))
    )
    (net (code "153") (name "unconnected-(M1-IO_N-Pad39)") (class "Default")
      (node (ref "M1") (pin "39") (pinfunction "IO_N_39") (pintype "passive+no_connect"))
    )
    (net (code "154") (name "unconnected-(M1-IO_N-Pad42)") (class "Default")
      (node (ref "M1") (pin "42") (pinfunction "IO_N_42") (pintype "passive+no_connect"))
    )
    (net (code "155") (name "unconnected-(M1-IO_N-Pad45)") (class "Default")
      (node (ref "M1") (pin "45") (pinfunction "IO_N_45") (pintype "passive+no_connect"))
    )
    (net (code "156") (name "unconnected-(M1-IO_N-Pad54)") (class "Default")
      (node (ref "M1") (pin "54") (pinfunction "IO_N_54") (pintype "passive+no_connect"))
    )
    (net (code "157") (name "unconnected-(M1-IO_N-Pad57)") (class "Default")
      (node (ref "M1") (pin "57") (pinfunction "IO_N_57") (pintype "passive+no_connect"))
    )
    (net (code "158") (name "unconnected-(M1-IO_N-Pad60)") (class "Default")
      (node (ref "M1") (pin "60") (pinfunction "IO_N_60") (pintype "passive+no_connect"))
    )
    (net (code "159") (name "unconnected-(M1-IO_N-Pad63)") (class "Default")
      (node (ref "M1") (pin "63") (pinfunction "IO_N_63") (pintype "passive+no_connect"))
    )
    (net (code "160") (name "unconnected-(M1-IO_N-Pad66)") (class "Default")
      (node (ref "M1") (pin "66") (pinfunction "IO_N_66") (pintype "passive+no_connect"))
    )
    (net (code "161") (name "unconnected-(M1-IO_N-Pad69)") (class "Default")
      (node (ref "M1") (pin "69") (pinfunction "IO_N_69") (pintype "passive+no_connect"))
    )
    (net (code "162") (name "unconnected-(M1-IO_N-Pad75)") (class "Default")
      (node (ref "M1") (pin "75") (pinfunction "IO_N_75") (pintype "passive+no_connect"))
    )
    (net (code "163") (name "unconnected-(M1-IO_N-Pad81)") (class "Default")
      (node (ref "M1") (pin "81") (pinfunction "IO_N_81") (pintype "passive+no_connect"))
    )
    (net (code "164") (name "unconnected-(M1-IO_N-Pad90)") (class "Default")
      (node (ref "M1") (pin "90") (pinfunction "IO_N_90") (pintype "passive+no_connect"))
    )
    (net (code "165") (name "unconnected-(M1-IO_N-Pad94)") (class "Default")
      (node (ref "M1") (pin "94") (pinfunction "IO_N_94") (pintype "passive+no_connect"))
    )
    (net (code "166") (name "unconnected-(M1-IO_N-Pad100)") (class "Default")
      (node (ref "M1") (pin "100") (pinfunction "IO_N_100") (pintype "passive+no_connect"))
    )
    (net (code "167") (name "unconnected-(M1-IO_P-Pad15)") (class "Default")
      (node (ref "M1") (pin "15") (pinfunction "IO_P_15") (pintype "passive"))
    )
    (net (code "168") (name "unconnected-(M1-IO_P-Pad19)") (class "Default")
      (node (ref "M1") (pin "19") (pinfunction "IO_P_19") (pintype "passive"))
    )
    (net (code "169") (name "unconnected-(M1-IO_P-Pad22)") (class "Default")
      (node (ref "M1") (pin "22") (pinfunction "IO_P_22") (pintype "passive"))
    )
    (net (code "170") (name "unconnected-(M1-IO_P-Pad25)") (class "Default")
      (node (ref "M1") (pin "25") (pinfunction "IO_P_25") (pintype "passive+no_connect"))
    )
    (net (code "171") (name "unconnected-(M1-IO_P-Pad28)") (class "Default")
      (node (ref "M1") (pin "28") (pinfunction "IO_P_28") (pintype "passive+no_connect"))
    )
    (net (code "172") (name "unconnected-(M1-IO_P-Pad31)") (class "Default")
      (node (ref "M1") (pin "31") (pinfunction "IO_P_31") (pintype "passive+no_connect"))
    )
    (net (code "173") (name "unconnected-(M1-IO_P-Pad34)") (class "Default")
      (node (ref "M1") (pin "34") (pinfunction "IO_P_34") (pintype "passive+no_connect"))
    )
    (net (code "174") (name "unconnected-(M1-IO_P-Pad37)") (class "Default")
      (node (ref "M1") (pin "37") (pinfunction "IO_P_37") (pintype "passive+no_connect"))
    )
    (net (code "175") (name "unconnected-(M1-IO_P-Pad40)") (class "Default")
      (node (ref "M1") (pin "40") (pinfunction "IO_P_40") (pintype "passive+no_connect"))
    )
    (net (code "176") (name "unconnected-(M1-IO_P-Pad43)") (class "Default")
      (node (ref "M1") (pin "43") (pinfunction "IO_P_43") (pintype "passive+no_connect"))
    )
    (net (code "177") (name "unconnected-(M1-IO_P-Pad52)") (class "Default")
      (node (ref "M1") (pin "52") (pinfunction "IO_P_52") (pintype "passive+no_connect"))
    )
    (net (code "178") (name "unconnected-(M1-IO_P-Pad55)") (class "Default")
      (node (ref "M1") (pin "55") (pinfunction "IO_P_55") (pintype "passive+no_connect"))
    )
    (net (code "179") (name "unconnected-(M1-IO_P-Pad58)") (class "Default")
      (node (ref "M1") (pin "58") (pinfunction "IO_P_58") (pintype "passive+no_connect"))
    )
    (net (code "180") (name "unconnected-(M1-IO_P-Pad61)") (class "Default")
      (node (ref "M1") (pin "61") (pinfunction "IO_P_61") (pintype "passive+no_connect"))
    )
    (net (code "181") (name "unconnected-(M1-IO_P-Pad64)") (class "Default")
      (node (ref "M1") (pin "64") (pinfunction "IO_P_64") (pintype "passive+no_connect"))
    )
    (net (code "182") (name "unconnected-(M1-IO_P-Pad67)") (class "Default")
      (node (ref "M1") (pin "67") (pinfunction "IO_P_67") (pintype "passive+no_connect"))
    )
    (net (code "183") (name "unconnected-(M1-IO_P-Pad73)") (class "Default")
      (node (ref "M1") (pin "73") (pinfunction "IO_P_73") (pintype "passive+no_connect"))
    )
    (net (code "184") (name "unconnected-(M1-IO_P-Pad79)") (class "Default")
      (node (ref "M1") (pin "79") (pinfunction "IO_P_79") (pintype "passive+no_connect"))
    )
    (net (code "185") (name "unconnected-(M1-IO_P-Pad88)") (class "Default")
      (node (ref "M1") (pin "88") (pinfunction "IO_P_88") (pintype "passive+no_connect"))
    )
    (net (code "186") (name "unconnected-(M1-IO_P-Pad92)") (class "Default")
      (node (ref "M1") (pin "92") (pinfunction "IO_P_92") (pintype "passive+no_connect"))
    )
    (net (code "187") (name "unconnected-(M1-PCLK_N-Pad48)") (class "Default")
      (node (ref "M1") (pin "48") (pinfunction "PCLK_N_48") (pintype "passive+no_connect"))
    )
    (net (code "188") (name "unconnected-(M1-PCLK_N-Pad87)") (class "Default")
      (node (ref "M1") (pin "87") (pinfunction "PCLK_N_87") (pintype "passive+no_connect"))
    )
    (net (code "189") (name "unconnected-(M1-PCLK_P-Pad46)") (class "Default")
      (node (ref "M1") (pin "46") (pinfunction "PCLK_P_46") (pintype "passive+no_connect"))
    )
    (net (code "190") (name "unconnected-(M1-PCLK_P-Pad85)") (class "Default")
      (node (ref "M1") (pin "85") (pinfunction "PCLK_P_85") (pintype "passive+no_connect"))
    )
    (net (code "191") (name "unconnected-(M1-RSVD-Pad110)") (class "Default")
      (node (ref "M1") (pin "110") (pinfunction "RSVD_110") (pintype "passive+no_connect"))
    )
    (net (code "192") (name "unconnected-(M1-SCLK_N-Pad18)") (class "Default")
      (node (ref "M1") (pin "18") (pinfunction "SCLK_N_18") (pintype "passive"))
    )
    (net (code "193") (name "unconnected-(M1-SCLK_N-Pad51)") (class "Default")
      (node (ref "M1") (pin "51") (pinfunction "SCLK_N_51") (pintype "passive+no_connect"))
    )
    (net (code "194") (name "unconnected-(M1-SCLK_N-Pad106)") (class "Default")
      (node (ref "M1") (pin "106") (pinfunction "SCLK_N_106") (pintype "passive+no_connect"))
    )
    (net (code "195") (name "unconnected-(M1-SCLK_P-Pad16)") (class "Default")
      (node (ref "M1") (pin "16") (pinfunction "SCLK_P_16") (pintype "passive"))
    )
    (net (code "196") (name "unconnected-(M1-SCLK_P-Pad49)") (class "Default")
      (node (ref "M1") (pin "49") (pinfunction "SCLK_P_49") (pintype "passive+no_connect"))
    )
    (net (code "197") (name "unconnected-(M1-SCLK_P-Pad104)") (class "Default")
      (node (ref "M1") (pin "104") (pinfunction "SCLK_P_104") (pintype "passive+no_connect"))
    )
    (net (code "198") (name "unconnected-(M1-USB_CPEN-Pad128)") (class "Default")
      (node (ref "M1") (pin "128") (pinfunction "USB_CPEN_128") (pintype "passive+no_connect"))
    )
    (net (code "199") (name "unconnected-(M1-USB_SSRX_N-Pad141)") (class "Default")
      (node (ref "M1") (pin "141") (pinfunction "USB_SSRX_N_141") (pintype "passive"))
    )
    (net (code "200") (name "unconnected-(M1-USB_SSRX_P-Pad137)") (class "Default")
      (node (ref "M1") (pin "137") (pinfunction "USB_SSRX_P_137") (pintype "passive"))
    )
    (net (code "201") (name "unconnected-(M1-USB_SSTX_N-Pad140)") (class "Default")
      (node (ref "M1") (pin "140") (pinfunction "USB_SSTX_N_140") (pintype "passive"))
    )
    (net (code "202") (name "unconnected-(M1-USB_SSTX_P-Pad136)") (class "Default")
      (node (ref "M1") (pin "136") (pinfunction "USB_SSTX_P_136") (pintype "passive"))
    )
    (net (code "203") (name "unconnected-(M1-VMON-Pad102)") (class "Default")
      (node (ref "M1") (pin "102") (pinfunction "VMON_102") (pintype "passive+no_connect"))
    )
    (net (code "204") (name "unconnected-(M1-VOUT-Pad62)") (class "Default")
      (node (ref "M1") (pin "62") (pinfunction "VOUT_62") (pintype "power_in"))
    )
    (net (code "205") (name "unconnected-(M1-VOUT-Pad65)") (class "Default")
      (node (ref "M1") (pin "65") (pinfunction "VOUT_65") (pintype "power_in+no_connect"))
    )
    (net (code "206") (name "unconnected-(M1-VOUT-Pad89)") (class "Default")
      (node (ref "M1") (pin "89") (pinfunction "VOUT_89") (pintype "power_in+no_connect"))
    )
    (net (code "207") (name "unconnected-(M2-IO_N-Pad9)") (class "Default")
      (node (ref "M2") (pin "9") (pinfunction "IO_N_9") (pintype "passive+no_connect"))
    )
    (net (code "208") (name "unconnected-(M2-IO_N-Pad47)") (class "Default")
      (node (ref "M2") (pin "47") (pinfunction "IO_N_47") (pintype "passive+no_connect"))
    )
    (net (code "209") (name "unconnected-(M2-IO_N-Pad50)") (class "Default")
      (node (ref "M2") (pin "50") (pinfunction "IO_N_50") (pintype "passive"))
    )
    (net (code "210") (name "unconnected-(M2-IO_N-Pad53)") (class "Default")
      (node (ref "M2") (pin "53") (pinfunction "IO_N_53") (pintype "passive+no_connect"))
    )
    (net (code "211") (name "unconnected-(M2-IO_N-Pad56)") (class "Default")
      (node (ref "M2") (pin "56") (pinfunction "IO_N_56") (pintype "passive+no_connect"))
    )
    (net (code "212") (name "unconnected-(M2-IO_N-Pad62)") (class "Default")
      (node (ref "M2") (pin "62") (pinfunction "IO_N_62") (pintype "passive"))
    )
    (net (code "213") (name "unconnected-(M2-IO_N-Pad65)") (class "Default")
      (node (ref "M2") (pin "65") (pinfunction "IO_N_65") (pintype "passive+no_connect"))
    )
    (net (code "214") (name "unconnected-(M2-IO_N-Pad68)") (class "Default")
      (node (ref "M2") (pin "68") (pinfunction "IO_N_68") (pintype "passive"))
    )
    (net (code "215") (name "unconnected-(M2-IO_N-Pad71)") (class "Default")
      (node (ref "M2") (pin "71") (pinfunction "IO_N_71") (pintype "passive+no_connect"))
    )
    (net (code "216") (name "unconnected-(M2-IO_P-Pad7)") (class "Default")
      (node (ref "M2") (pin "7") (pinfunction "IO_P_7") (pintype "passive+no_connect"))
    )
    (net (code "217") (name "unconnected-(M2-IO_P-Pad45)") (class "Default")
      (node (ref "M2") (pin "45") (pinfunction "IO_P_45") (pintype "passive+no_connect"))
    )
    (net (code "218") (name "unconnected-(M2-IO_P-Pad48)") (class "Default")
      (node (ref "M2") (pin "48") (pinfunction "IO_P_48") (pintype "passive"))
    )
    (net (code "219") (name "unconnected-(M2-IO_P-Pad51)") (class "Default")
      (node (ref "M2") (pin "51") (pinfunction "IO_P_51") (pintype "passive+no_connect"))
    )
    (net (code "220") (name "unconnected-(M2-IO_P-Pad54)") (class "Default")
      (node (ref "M2") (pin "54") (pinfunction "IO_P_54") (pintype "passive+no_connect"))
    )
    (net (code "221") (name "unconnected-(M2-IO_P-Pad60)") (class "Default")
      (node (ref "M2") (pin "60") (pinfunction "IO_P_60") (pintype "passive"))
    )
    (net (code "222") (name "unconnected-(M2-IO_P-Pad63)") (class "Default")
      (node (ref "M2") (pin "63") (pinfunction "IO_P_63") (pintype "passive+no_connect"))
    )
    (net (code "223") (name "unconnected-(M2-IO_P-Pad66)") (class "Default")
      (node (ref "M2") (pin "66") (pinfunction "IO_P_66") (pintype "passive"))
    )
    (net (code "224") (name "unconnected-(M2-IO_P-Pad69)") (class "Default")
      (node (ref "M2") (pin "69") (pinfunction "IO_P_69") (pintype "passive+no_connect"))
    )
    (net (code "225") (name "unconnected-(M2-MGT_CLK_N-Pad6)") (class "Default")
      (node (ref "M2") (pin "6") (pinfunction "MGT_CLK_N_6") (pintype "passive+no_connect"))
    )
    (net (code "226") (name "unconnected-(M2-MGT_CLK_N-Pad12)") (class "Default")
      (node (ref "M2") (pin "12") (pinfunction "MGT_CLK_N_12") (pintype "passive+no_connect"))
    )
    (net (code "227") (name "unconnected-(M2-MGT_CLK_P-Pad4)") (class "Default")
      (node (ref "M2") (pin "4") (pinfunction "MGT_CLK_P_4") (pintype "passive+no_connect"))
    )
    (net (code "228") (name "unconnected-(M2-MGT_CLK_P-Pad10)") (class "Default")
      (node (ref "M2") (pin "10") (pinfunction "MGT_CLK_P_10") (pintype "passive+no_connect"))
    )
    (net (code "229") (name "unconnected-(M2-MGT_RX_N-Pad20)") (class "Default")
      (node (ref "M2") (pin "20") (pinfunction "MGT_RX_N_20") (pintype "passive+no_connect"))
    )
    (net (code "230") (name "unconnected-(M2-MGT_RX_N-Pad28)") (class "Default")
      (node (ref "M2") (pin "28") (pinfunction "MGT_RX_N_28") (pintype "passive+no_connect"))
    )
    (net (code "231") (name "unconnected-(M2-MGT_RX_N-Pad44)") (class "Default")
      (node (ref "M2") (pin "44") (pinfunction "MGT_RX_N_44") (pintype "passive+no_connect"))
    )
    (net (code "232") (name "unconnected-(M2-MGT_RX_P-Pad16)") (class "Default")
      (node (ref "M2") (pin "16") (pinfunction "MGT_RX_P_16") (pintype "passive+no_connect"))
    )
    (net (code "233") (name "unconnected-(M2-MGT_RX_P-Pad24)") (class "Default")
      (node (ref "M2") (pin "24") (pinfunction "MGT_RX_P_24") (pintype "passive+no_connect"))
    )
    (net (code "234") (name "unconnected-(M2-MGT_RX_P-Pad40)") (class "Default")
      (node (ref "M2") (pin "40") (pinfunction "MGT_RX_P_40") (pintype "passive+no_connect"))
    )
    (net (code "235") (name "unconnected-(M2-MGT_TX_N-Pad41)") (class "Default")
      (node (ref "M2") (pin "41") (pinfunction "MGT_TX_N_41") (pintype "passive+no_connect"))
    )
    (net (code "236") (name "unconnected-(M2-MGT_TX_P-Pad37)") (class "Default")
      (node (ref "M2") (pin "37") (pinfunction "MGT_TX_P_37") (pintype "passive+no_connect"))
    )
    (net (code "237") (name "unconnected-(M2-SCLK_N-Pad5)") (class "Default")
      (node (ref "M2") (pin "5") (pinfunction "SCLK_N_5") (pintype "passive+no_connect"))
    )
    (net (code "238") (name "unconnected-(M2-SCLK_P-Pad3)") (class "Default")
      (node (ref "M2") (pin "3") (pinfunction "SCLK_P_3") (pintype "passive+no_connect"))
    )
    (net (code "239") (name "unconnected-(M2-VMON-Pad8)") (class "Default")
      (node (ref "M2") (pin "8") (pinfunction "VMON_8") (pintype "passive"))
    )
    (net (code "240") (name "unconnected-(M2-VMON-Pad167)") (class "Default")
      (node (ref "M2") (pin "167") (pinfunction "VMON_167") (pintype "passive"))
    )
    (net (code "241") (name "unconnected-(M2-VMON-Pad168)") (class "Default")
      (node (ref "M2") (pin "168") (pinfunction "VMON_168") (pintype "passive+no_connect"))
    )
    (net (code "242") (name "unconnected-(M2-VOUT_3V3-Pad55)") (class "Default")
      (node (ref "M2") (pin "55") (pinfunction "VOUT_3V3_55") (pintype "passive+no_connect"))
    )
    (net (code "243") (name "unconnected-(M2-VOUT_3V3-Pad79)") (class "Default")
      (node (ref "M2") (pin "79") (pinfunction "VOUT_3V3_79") (pintype "passive+no_connect"))
    )
    (net (code "244") (name "unconnected-(M2-VOUT_3V3-Pad115)") (class "Default")
      (node (ref "M2") (pin "115") (pinfunction "VOUT_3V3_115") (pintype "passive+no_connect"))
    )
    (net (code "245") (name "unconnected-(M2-VOUT_3V3-Pad127)") (class "Default")
      (node (ref "M2") (pin "127") (pinfunction "VOUT_3V3_127") (pintype "passive+no_connect"))
    )
    (net (code "246") (name "unconnected-(M2-VOUT_3V3-Pad152)") (class "Default")
      (node (ref "M2") (pin "152") (pinfunction "VOUT_3V3_152") (pintype "passive+no_connect"))
    )
    (net (code "247") (name "unconnected-(M2-VOUT_3V3-Pad155)") (class "Default")
      (node (ref "M2") (pin "155") (pinfunction "VOUT_3V3_155") (pintype "passive+no_connect"))
    )
    (net (code "248") (name "unconnected-(SP1-Pad1)") (class "Default")
      (node (ref "SP1") (pin "1") (pinfunction "1_1") (pintype "passive"))
    )
    (net (code "249") (name "unconnected-(SP2-Pad1)") (class "Default")
      (node (ref "SP2") (pin "1") (pinfunction "1_1") (pintype "passive"))
    )
    (net (code "250") (name "unconnected-(SP3-Pad1)") (class "Default")
      (node (ref "SP3") (pin "1") (pinfunction "1_1") (pintype "passive"))
    )
    (net (code "251") (name "unconnected-(SP4-Pad1)") (class "Default")
      (node (ref "SP4") (pin "1") (pinfunction "1_1") (pintype "passive"))
    )
  )
)
